# Encoder.net
KiCad netlist of a schematic drawn in Altium Designer
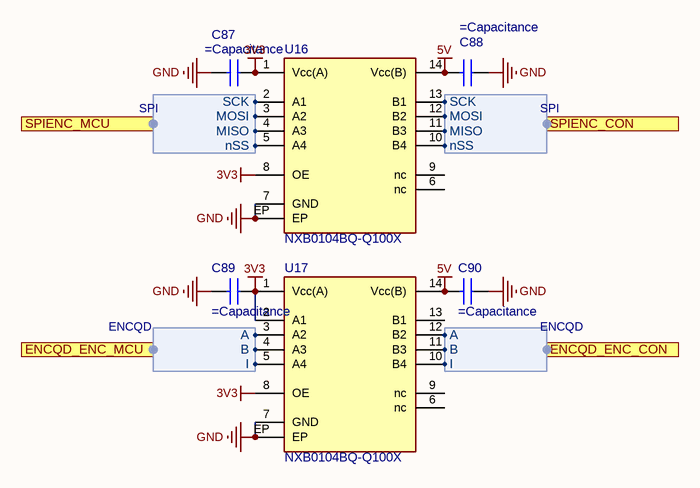
[diagram p0: Encoder.SchDoc]

(export (version "E")
  (design (tool "Eeschema 10.0.6"))
  (components
    (comp (ref "C87")
      (value "~")
      (footprint "C0402")
      (description "CAP CER 0.1UF 50V X7R 0402")
      (fields
        (field (name "MANUFACTURER") "Walsin Technologies")
        (field (name "MANUFACTURER PART NUMBER") "0402B104K500CT")
      )
      (libsource (lib "Capacitors") (part "CAP0402-0.1uF-50V"))
    )
    (comp (ref "C88")
      (value "~")
      (footprint "C0402")
      (description "CAP CER 0.1UF 50V X7R 0402")
      (fields
        (field (name "MANUFACTURER") "Walsin Technologies")
        (field (name "MANUFACTURER PART NUMBER") "0402B104K500CT")
      )
      (libsource (lib "Capacitors") (part "CAP0402-0.1uF-50V"))
    )
    (comp (ref "C89")
      (value "~")
      (footprint "C0402")
      (description "CAP CER 0.1UF 50V X7R 0402")
      (fields
        (field (name "MANUFACTURER") "Walsin Technologies")
        (field (name "MANUFACTURER PART NUMBER") "0402B104K500CT")
      )
      (libsource (lib "Capacitors") (part "CAP0402-0.1uF-50V"))
    )
    (comp (ref "C90")
      (value "~")
      (footprint "C0402")
      (description "CAP CER 0.1UF 50V X7R 0402")
      (fields
        (field (name "MANUFACTURER") "Walsin Technologies")
        (field (name "MANUFACTURER PART NUMBER") "0402B104K500CT")
      )
      (libsource (lib "Capacitors") (part "CAP0402-0.1uF-50V"))
    )
    (comp (ref "U16")
      (value "NXB0104BQ-Q100X")
      (footprint "DHVQFN14")
      (description "1.65V~5.5V 1 2 1.2V~3.6V 100Mbps DHVQFN-14-EP(2.5x3) Translators / Level Shifters ROHS")
      (fields (field (name "MANUFACTURER") "Nexperia"))
      (libsource (lib "IC") (part "NXB0104BQ-Q100"))
    )
    (comp (ref "U17")
      (value "NXB0104BQ-Q100X")
      (footprint "DHVQFN14")
      (description "1.65V~5.5V 1 2 1.2V~3.6V 100Mbps DHVQFN-14-EP(2.5x3) Translators / Level Shifters ROHS")
      (fields (field (name "MANUFACTURER") "Nexperia"))
      (libsource (lib "IC") (part "NXB0104BQ-Q100"))
    )
  )
  (nets
    (net (code "5") (name "3V3") (class "Default")
      (node (ref "C87") (pin "1") (pinfunction "1_1") (pintype "passive"))
      (node (ref "C89") (pin "1") (pinfunction "1_1") (pintype "passive"))
      (node (ref "U16") (pin "1") (pinfunction "Vcc(A)_1") (pintype "passive"))
      (node (ref "U16") (pin "8") (pinfunction "OE_8") (pintype "passive"))
      (node (ref "U17") (pin "1") (pinfunction "Vcc(A)_1") (pintype "passive"))
      (node (ref "U17") (pin "2") (pinfunction "A1_2") (pintype "passive"))
      (node (ref "U17") (pin "8") (pinfunction "OE_8") (pintype "passive"))
    )
    (net (code "6") (name "5V") (class "Default")
      (node (ref "C88") (pin "2") (pinfunction "2_2") (pintype "passive"))
      (node (ref "C90") (pin "2") (pinfunction "2_2") (pintype "passive"))
      (node (ref "U16") (pin "14") (pinfunction "Vcc(B)_14") (pintype "passive"))
      (node (ref "U17") (pin "14") (pinfunction "Vcc(B)_14") (pintype "passive"))
    )
    (net (code "7") (name "GND") (class "Default")
      (node (ref "C87") (pin "2") (pinfunction "2_2") (pintype "passive"))
      (node (ref "C88") (pin "1") (pinfunction "1_1") (pintype "passive"))
      (node (ref "C89") (pin "2") (pinfunction "2_2") (pintype "passive"))
      (node (ref "C90") (pin "1") (pinfunction "1_1") (pintype "passive"))
      (node (ref "U16") (pin "7") (pinfunction "GND_7") (pintype "passive"))
      (node (ref "U16") (pin "EP") (pinfunction "EP_EP") (pintype "passive"))
      (node (ref "U17") (pin "7") (pinfunction "GND_7") (pintype "passive"))
      (node (ref "U17") (pin "EP") (pinfunction "EP_EP") (pintype "passive"))
    )
    (net (code "8") (name "unconnected-(U16-A1-Pad2)") (class "Default")
      (node (ref "U16") (pin "2") (pinfunction "A1_2") (pintype "passive"))
    )
    (net (code "9") (name "unconnected-(U16-A2-Pad3)") (class "Default")
      (node (ref "U16") (pin "3") (pinfunction "A2_3") (pintype "passive"))
    )
    (net (code "10") (name "unconnected-(U16-A3-Pad4)") (class "Default")
      (node (ref "U16") (pin "4") (pinfunction "A3_4") (pintype "passive"))
    )
    (net (code "11") (name "unconnected-(U16-A4-Pad5)") (class "Default")
      (node (ref "U16") (pin "5") (pinfunction "A4_5") (pintype "passive"))
    )
    (net (code "12") (name "unconnected-(U16-B1-Pad13)") (class "Default")
      (node (ref "U16") (pin "13") (pinfunction "B1_13") (pintype "passive"))
    )
    (net (code "13") (name "unconnected-(U16-B2-Pad12)") (class "Default")
      (node (ref "U16") (pin "12") (pinfunction "B2_12") (pintype "passive"))
    )
    (net (code "14") (name "unconnected-(U16-B3-Pad11)") (class "Default")
      (node (ref "U16") (pin "11") (pinfunction "B3_11") (pintype "passive"))
    )
    (net (code "15") (name "unconnected-(U16-B4-Pad10)") (class "Default")
      (node (ref "U16") (pin "10") (pinfunction "B4_10") (pintype "passive"))
    )
    (net (code "16") (name "unconnected-(U16-nc-Pad6)") (class "Default")
      (node (ref "U16") (pin "6") (pinfunction "nc_6") (pintype "passive"))
    )
    (net (code "17") (name "unconnected-(U16-nc-Pad9)") (class "Default")
      (node (ref "U16") (pin "9") (pinfunction "nc_9") (pintype "passive"))
    )
    (net (code "18") (name "unconnected-(U17-A2-Pad3)") (class "Default")
      (node (ref "U17") (pin "3") (pinfunction "A2_3") (pintype "passive"))
    )
    (net (code "19") (name "unconnected-(U17-A3-Pad4)") (class "Default")
      (node (ref "U17") (pin "4") (pinfunction "A3_4") (pintype "passive"))
    )
    (net (code "20") (name "unconnected-(U17-A4-Pad5)") (class "Default")
      (node (ref "U17") (pin "5") (pinfunction "A4_5") (pintype "passive"))
    )
    (net (code "21") (name "unconnected-(U17-B1-Pad13)") (class "Default")
      (node (ref "U17") (pin "13") (pinfunction "B1_13") (pintype "passive"))
    )
    (net (code "22") (name "unconnected-(U17-B2-Pad12)") (class "Default")
      (node (ref "U17") (pin "12") (pinfunction "B2_12") (pintype "passive"))
    )
    (net (code "23") (name "unconnected-(U17-B3-Pad11)") (class "Default")
      (node (ref "U17") (pin "11") (pinfunction "B3_11") (pintype "passive"))
    )
    (net (code "24") (name "unconnected-(U17-B4-Pad10)") (class "Default")
      (node (ref "U17") (pin "10") (pinfunction "B4_10") (pintype "passive"))
    )
    (net (code "25") (name "unconnected-(U17-nc-Pad6)") (class "Default")
      (node (ref "U17") (pin "6") (pinfunction "nc_6") (pintype "passive"))
    )
    (net (code "26") (name "unconnected-(U17-nc-Pad9)") (class "Default")
      (node (ref "U17") (pin "9") (pinfunction "nc_9") (pintype "passive"))
    )
  )
)
